# STM32_MPU_IOs.net
KiCad netlist of a schematic drawn in Altium Designer
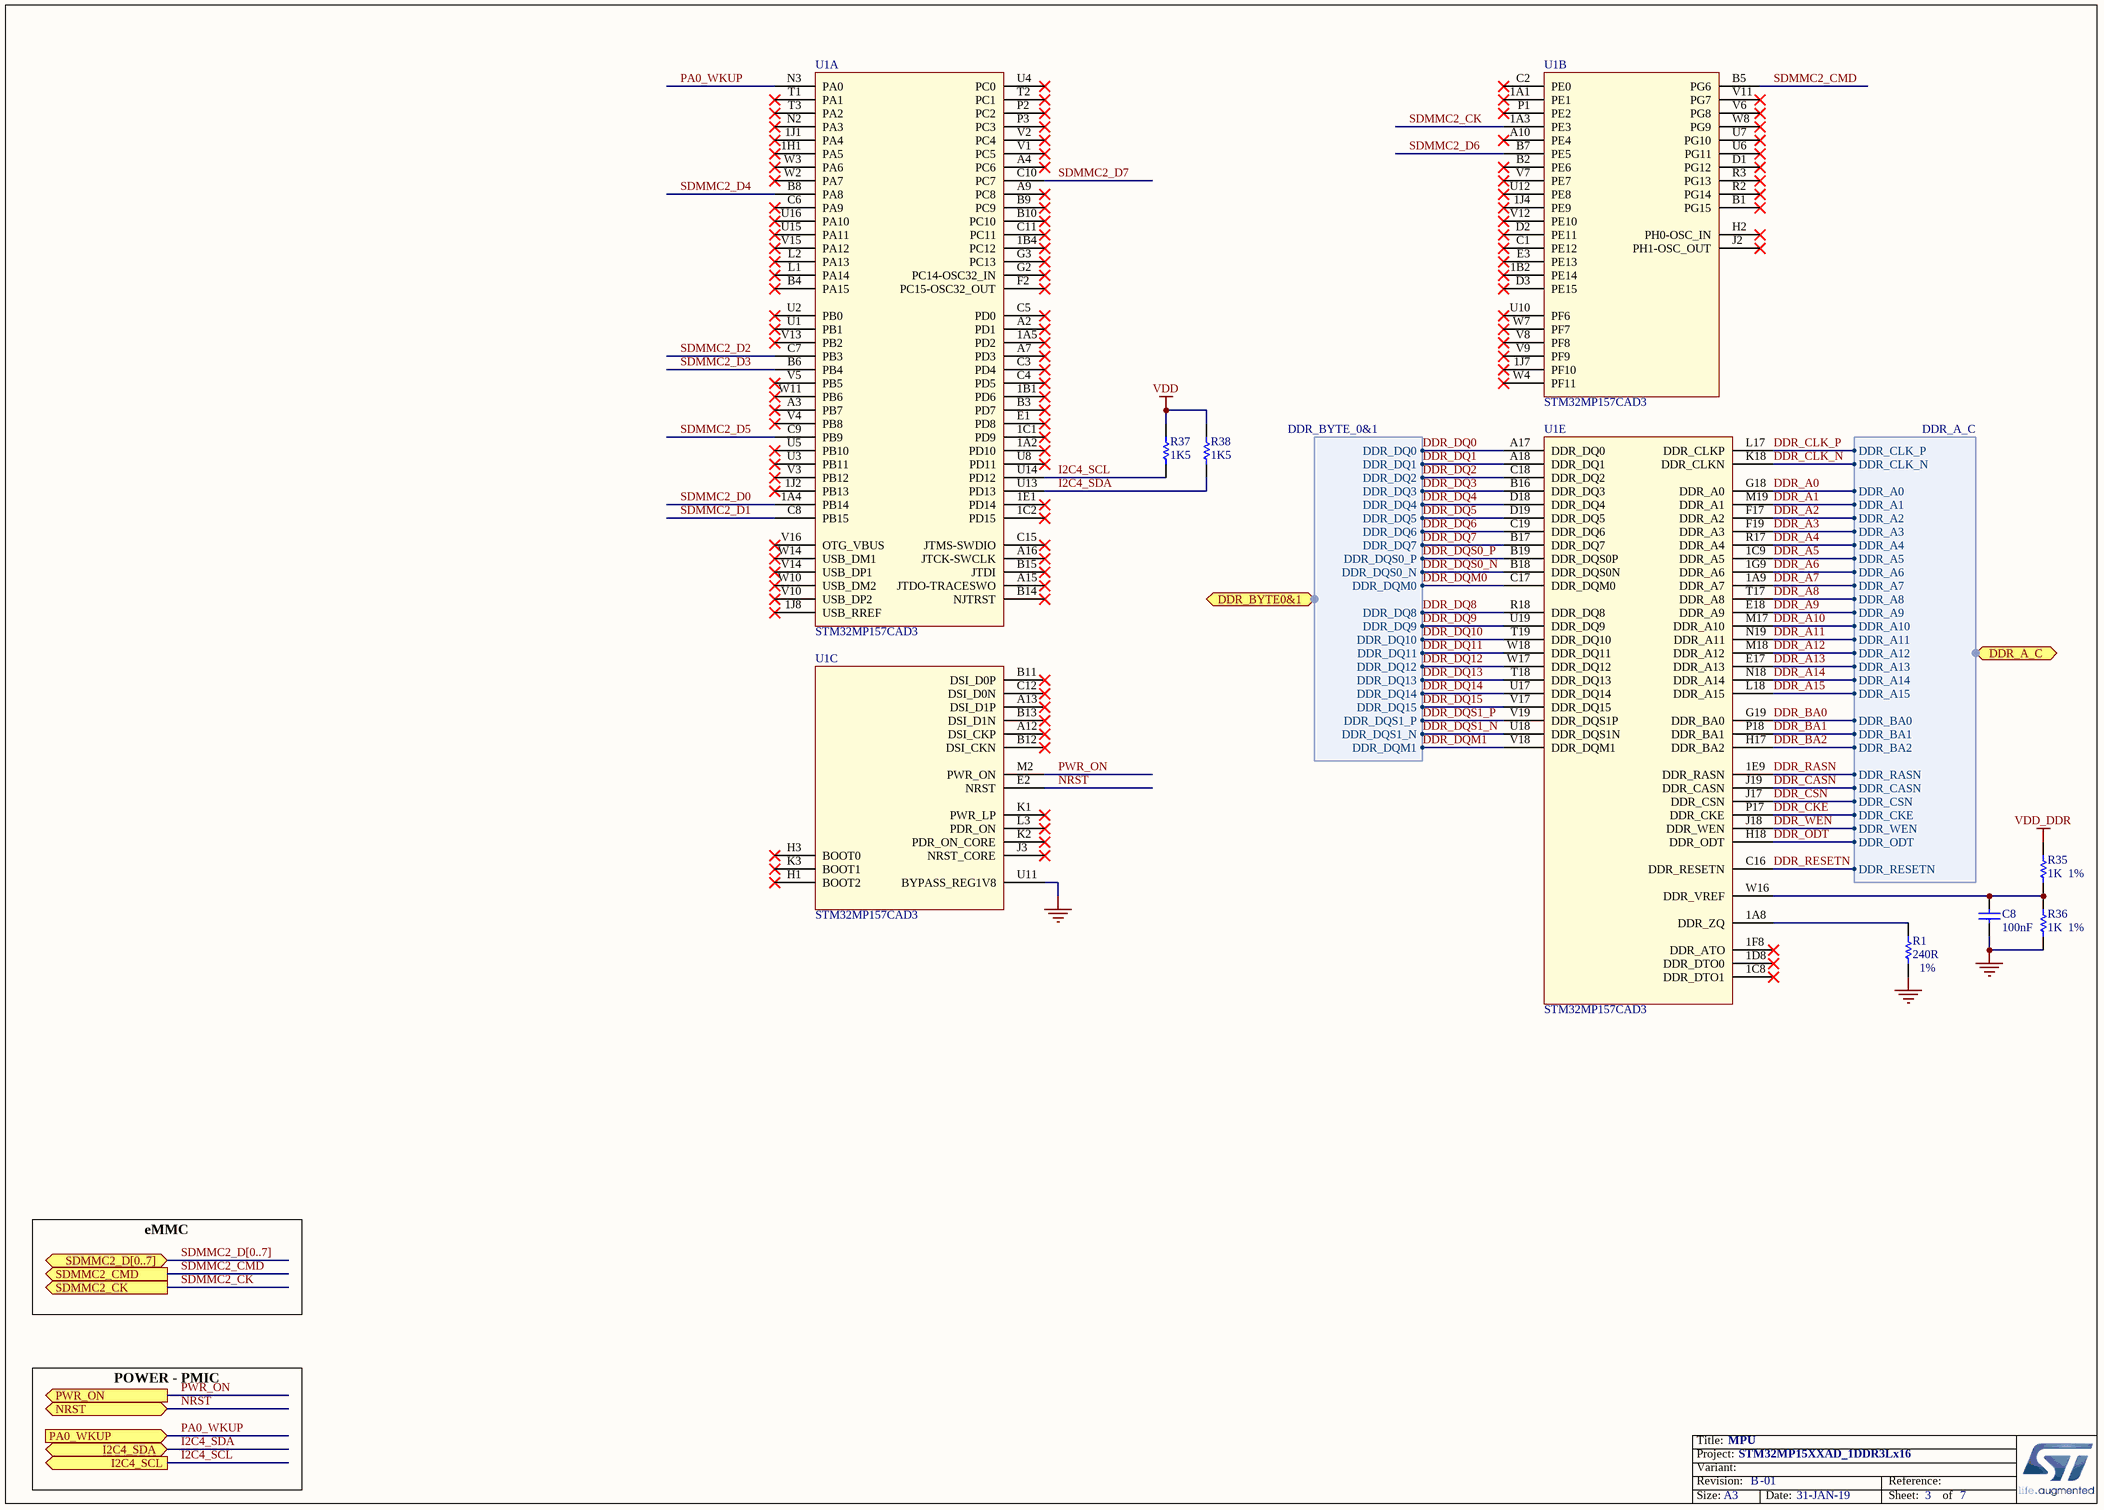
[diagram p0: STM32_MPU_IOs.SchDoc]

(export (version "E")
  (design (tool "Eeschema 10.0.6"))
  (components
    (comp (ref "C8")
      (value "100nF")
      (footprint "C0402")
      (description "Capacitor, MLCC, 100nF, 16V, X7R, 10%, 0402, T=0.5mm")
      (fields
        (field (name "INTERNAL_PART_NUMBER") "MCD-00006")
        (field (name "MANUFACTURER_PART_NUMBER") "CC0402KRX7R7BB104")
        (field (name "PROVIDED_BY") "SUBCO")
      )
      (libsource (lib "MCD_PARTS_database") (part "Capacitor"))
    )
    (comp (ref "R1")
      (value "240R")
      (footprint "R0402")
      (description "Resistor,240R,0402,1%,1/16W")
      (fields
        (field (name "INTERNAL_PART_NUMBER") "MCD-00120")
        (field (name "MANUFACTURER_PART_NUMBER") "RC0402FR-07240RL")
        (field (name "PROVIDED_BY") "SUBCO")
      )
      (libsource (lib "MCD_PARTS_database") (part "Resistor"))
    )
    (comp (ref "R35")
      (value "1K")
      (footprint "R0402")
      (description "Resistor,1K,0402,1%,1/16W")
      (fields
        (field (name "INTERNAL_PART_NUMBER") "MCD-00061")
        (field (name "MANUFACTURER_PART_NUMBER") "RC0402FR-071KL")
        (field (name "PROVIDED_BY") "SUBCO")
      )
      (libsource (lib "MCD_PARTS_database") (part "Resistor"))
    )
    (comp (ref "R36")
      (value "1K")
      (footprint "R0402")
      (description "Resistor,1K,0402,1%,1/16W")
      (fields
        (field (name "INTERNAL_PART_NUMBER") "MCD-00061")
        (field (name "MANUFACTURER_PART_NUMBER") "RC0402FR-071KL")
        (field (name "PROVIDED_BY") "SUBCO")
      )
      (libsource (lib "MCD_PARTS_database") (part "Resistor"))
    )
    (comp (ref "R37")
      (value "1K5")
      (footprint "R0402")
      (description "Resistor,1K5,0402,1%,1/16W")
      (fields
        (field (name "INTERNAL_PART_NUMBER") "MCD-00068")
        (field (name "MANUFACTURER_PART_NUMBER") "RC0402FR-071K5L")
        (field (name "PROVIDED_BY") "SUBCO")
      )
      (libsource (lib "MCD_PARTS_database") (part "Resistor"))
    )
    (comp (ref "R38")
      (value "1K5")
      (footprint "R0402")
      (description "Resistor,1K5,0402,1%,1/16W")
      (fields
        (field (name "INTERNAL_PART_NUMBER") "MCD-00068")
        (field (name "MANUFACTURER_PART_NUMBER") "RC0402FR-071K5L")
        (field (name "PROVIDED_BY") "SUBCO")
      )
      (libsource (lib "MCD_PARTS_database") (part "Resistor"))
    )
    (comp (ref "U1")
      (value "STM32MP157CAD3")
      (footprint "ICC_TFBGA257_10X10_STM32MP157CAD3_P050-065")
      (description "MPU TFBGA10x10 secure boot+crypto")
      (fields
        (field (name "INTERNAL_PART_NUMBER") "MCD-01144")
        (field (name "MANUFACTURER") "STMICROELECTRONICS")
        (field (name "PROVIDED_BY") "SUBCO with ST control")
      )
      (libsource (lib "MCD_PARTS_database") (part "STM32MP157CAD3"))
    )
  )
  (nets
    (net (code "3") (name "/DDR_A0") (class "Default")
      (node (ref "U1") (pin "G18") (pinfunction "DDR_A0_G18") (pintype "passive"))
    )
    (net (code "4") (name "/DDR_A1") (class "Default")
      (node (ref "U1") (pin "M19") (pinfunction "DDR_A1_M19") (pintype "passive"))
    )
    (net (code "5") (name "/DDR_A2") (class "Default")
      (node (ref "U1") (pin "F17") (pinfunction "DDR_A2_F17") (pintype "passive"))
    )
    (net (code "6") (name "/DDR_A3") (class "Default")
      (node (ref "U1") (pin "F19") (pinfunction "DDR_A3_F19") (pintype "passive"))
    )
    (net (code "7") (name "/DDR_A4") (class "Default")
      (node (ref "U1") (pin "R17") (pinfunction "DDR_A4_R17") (pintype "passive"))
    )
    (net (code "8") (name "/DDR_A5") (class "Default")
      (node (ref "U1") (pin "1C9") (pinfunction "DDR_A5_1C9") (pintype "passive"))
    )
    (net (code "9") (name "/DDR_A6") (class "Default")
      (node (ref "U1") (pin "1G9") (pinfunction "DDR_A6_1G9") (pintype "passive"))
    )
    (net (code "10") (name "/DDR_A7") (class "Default")
      (node (ref "U1") (pin "1A9") (pinfunction "DDR_A7_1A9") (pintype "passive"))
    )
    (net (code "11") (name "/DDR_A8") (class "Default")
      (node (ref "U1") (pin "T17") (pinfunction "DDR_A8_T17") (pintype "passive"))
    )
    (net (code "12") (name "/DDR_A9") (class "Default")
      (node (ref "U1") (pin "E18") (pinfunction "DDR_A9_E18") (pintype "passive"))
    )
    (net (code "13") (name "/DDR_A10") (class "Default")
      (node (ref "U1") (pin "M17") (pinfunction "DDR_A10_M17") (pintype "passive"))
    )
    (net (code "14") (name "/DDR_A11") (class "Default")
      (node (ref "U1") (pin "N19") (pinfunction "DDR_A11_N19") (pintype "passive"))
    )
    (net (code "15") (name "/DDR_A12") (class "Default")
      (node (ref "U1") (pin "M18") (pinfunction "DDR_A12_M18") (pintype "passive"))
    )
    (net (code "16") (name "/DDR_A13") (class "Default")
      (node (ref "U1") (pin "E17") (pinfunction "DDR_A13_E17") (pintype "passive"))
    )
    (net (code "17") (name "/DDR_A14") (class "Default")
      (node (ref "U1") (pin "N18") (pinfunction "DDR_A14_N18") (pintype "passive"))
    )
    (net (code "18") (name "/DDR_A15") (class "Default")
      (node (ref "U1") (pin "L18") (pinfunction "DDR_A15_L18") (pintype "passive"))
    )
    (net (code "19") (name "/DDR_BA0") (class "Default")
      (node (ref "U1") (pin "G19") (pinfunction "DDR_BA0_G19") (pintype "passive"))
    )
    (net (code "20") (name "/DDR_BA1") (class "Default")
      (node (ref "U1") (pin "P18") (pinfunction "DDR_BA1_P18") (pintype "passive"))
    )
    (net (code "21") (name "/DDR_BA2") (class "Default")
      (node (ref "U1") (pin "H17") (pinfunction "DDR_BA2_H17") (pintype "passive"))
    )
    (net (code "22") (name "/DDR_CASN") (class "Default")
      (node (ref "U1") (pin "J19") (pinfunction "DDR_CASN_J19") (pintype "passive"))
    )
    (net (code "23") (name "/DDR_CKE") (class "Default")
      (node (ref "U1") (pin "P17") (pinfunction "DDR_CKE_P17") (pintype "passive"))
    )
    (net (code "24") (name "/DDR_CLK_N") (class "Default")
      (node (ref "U1") (pin "K18") (pinfunction "DDR_CLKN_K18") (pintype "passive"))
    )
    (net (code "25") (name "/DDR_CLK_P") (class "Default")
      (node (ref "U1") (pin "L17") (pinfunction "DDR_CLKP_L17") (pintype "passive"))
    )
    (net (code "26") (name "/DDR_CSN") (class "Default")
      (node (ref "U1") (pin "J17") (pinfunction "DDR_CSN_J17") (pintype "passive"))
    )
    (net (code "27") (name "/DDR_DQ0") (class "Default")
      (node (ref "U1") (pin "A17") (pinfunction "DDR_DQ0_A17") (pintype "passive"))
    )
    (net (code "28") (name "/DDR_DQ1") (class "Default")
      (node (ref "U1") (pin "A18") (pinfunction "DDR_DQ1_A18") (pintype "passive"))
    )
    (net (code "29") (name "/DDR_DQ2") (class "Default")
      (node (ref "U1") (pin "C18") (pinfunction "DDR_DQ2_C18") (pintype "passive"))
    )
    (net (code "30") (name "/DDR_DQ3") (class "Default")
      (node (ref "U1") (pin "B16") (pinfunction "DDR_DQ3_B16") (pintype "passive"))
    )
    (net (code "31") (name "/DDR_DQ4") (class "Default")
      (node (ref "U1") (pin "D18") (pinfunction "DDR_DQ4_D18") (pintype "passive"))
    )
    (net (code "32") (name "/DDR_DQ5") (class "Default")
      (node (ref "U1") (pin "D19") (pinfunction "DDR_DQ5_D19") (pintype "passive"))
    )
    (net (code "33") (name "/DDR_DQ6") (class "Default")
      (node (ref "U1") (pin "C19") (pinfunction "DDR_DQ6_C19") (pintype "passive"))
    )
    (net (code "34") (name "/DDR_DQ7") (class "Default")
      (node (ref "U1") (pin "B17") (pinfunction "DDR_DQ7_B17") (pintype "passive"))
    )
    (net (code "35") (name "/DDR_DQ8") (class "Default")
      (node (ref "U1") (pin "R18") (pinfunction "DDR_DQ8_R18") (pintype "passive"))
    )
    (net (code "36") (name "/DDR_DQ9") (class "Default")
      (node (ref "U1") (pin "U19") (pinfunction "DDR_DQ9_U19") (pintype "passive"))
    )
    (net (code "37") (name "/DDR_DQ10") (class "Default")
      (node (ref "U1") (pin "T19") (pinfunction "DDR_DQ10_T19") (pintype "passive"))
    )
    (net (code "38") (name "/DDR_DQ11") (class "Default")
      (node (ref "U1") (pin "W18") (pinfunction "DDR_DQ11_W18") (pintype "passive"))
    )
    (net (code "39") (name "/DDR_DQ12") (class "Default")
      (node (ref "U1") (pin "W17") (pinfunction "DDR_DQ12_W17") (pintype "passive"))
    )
    (net (code "40") (name "/DDR_DQ13") (class "Default")
      (node (ref "U1") (pin "T18") (pinfunction "DDR_DQ13_T18") (pintype "passive"))
    )
    (net (code "41") (name "/DDR_DQ14") (class "Default")
      (node (ref "U1") (pin "U17") (pinfunction "DDR_DQ14_U17") (pintype "passive"))
    )
    (net (code "42") (name "/DDR_DQ15") (class "Default")
      (node (ref "U1") (pin "V17") (pinfunction "DDR_DQ15_V17") (pintype "passive"))
    )
    (net (code "43") (name "/DDR_DQM0") (class "Default")
      (node (ref "U1") (pin "C17") (pinfunction "DDR_DQM0_C17") (pintype "passive"))
    )
    (net (code "44") (name "/DDR_DQM1") (class "Default")
      (node (ref "U1") (pin "V18") (pinfunction "DDR_DQM1_V18") (pintype "passive"))
    )
    (net (code "45") (name "/DDR_DQS0_N") (class "Default")
      (node (ref "U1") (pin "B18") (pinfunction "DDR_DQS0N_B18") (pintype "passive"))
    )
    (net (code "46") (name "/DDR_DQS0_P") (class "Default")
      (node (ref "U1") (pin "B19") (pinfunction "DDR_DQS0P_B19") (pintype "passive"))
    )
    (net (code "47") (name "/DDR_DQS1_N") (class "Default")
      (node (ref "U1") (pin "U18") (pinfunction "DDR_DQS1N_U18") (pintype "passive"))
    )
    (net (code "48") (name "/DDR_DQS1_P") (class "Default")
      (node (ref "U1") (pin "V19") (pinfunction "DDR_DQS1P_V19") (pintype "passive"))
    )
    (net (code "49") (name "/DDR_ODT") (class "Default")
      (node (ref "U1") (pin "H18") (pinfunction "DDR_ODT_H18") (pintype "passive"))
    )
    (net (code "50") (name "/DDR_RASN") (class "Default")
      (node (ref "U1") (pin "1E9") (pinfunction "DDR_RASN_1E9") (pintype "passive"))
    )
    (net (code "51") (name "/DDR_RESETN") (class "Default")
      (node (ref "U1") (pin "C16") (pinfunction "DDR_RESETN_C16") (pintype "passive"))
    )
    (net (code "52") (name "/DDR_WEN") (class "Default")
      (node (ref "U1") (pin "J18") (pinfunction "DDR_WEN_J18") (pintype "passive"))
    )
    (net (code "53") (name "/I2C4_SCL") (class "Default")
      (node (ref "R37") (pin "2") (pinfunction "2_2") (pintype "passive"))
      (node (ref "U1") (pin "U14") (pinfunction "PD12_U14") (pintype "passive"))
    )
    (net (code "54") (name "/I2C4_SDA") (class "Default")
      (node (ref "R38") (pin "2") (pinfunction "2_2") (pintype "passive"))
      (node (ref "U1") (pin "U13") (pinfunction "PD13_U13") (pintype "passive"))
    )
    (net (code "55") (name "/NRST") (class "Default")
      (node (ref "U1") (pin "E2") (pinfunction "NRST_E2") (pintype "passive"))
    )
    (net (code "56") (name "/PA0_WKUP") (class "Default")
      (node (ref "U1") (pin "N3") (pinfunction "PA0_N3") (pintype "passive"))
    )
    (net (code "57") (name "/PWR_ON") (class "Default")
      (node (ref "U1") (pin "M2") (pinfunction "PWR_ON_M2") (pintype "passive"))
    )
    (net (code "58") (name "/SDMMC2_CK") (class "Default")
      (node (ref "U1") (pin "1A3") (pinfunction "PE3_1A3") (pintype "passive"))
    )
    (net (code "59") (name "/SDMMC2_CMD") (class "Default")
      (node (ref "U1") (pin "B5") (pinfunction "PG6_B5") (pintype "passive"))
    )
    (net (code "60") (name "/SDMMC2_D0") (class "Default")
      (node (ref "U1") (pin "1A4") (pinfunction "PB14_1A4") (pintype "passive"))
    )
    (net (code "61") (name "/SDMMC2_D1") (class "Default")
      (node (ref "U1") (pin "C8") (pinfunction "PB15_C8") (pintype "passive"))
    )
    (net (code "62") (name "/SDMMC2_D2") (class "Default")
      (node (ref "U1") (pin "C7") (pinfunction "PB3_C7") (pintype "passive"))
    )
    (net (code "63") (name "/SDMMC2_D3") (class "Default")
      (node (ref "U1") (pin "B6") (pinfunction "PB4_B6") (pintype "passive"))
    )
    (net (code "64") (name "/SDMMC2_D4") (class "Default")
      (node (ref "U1") (pin "B8") (pinfunction "PA8_B8") (pintype "passive"))
    )
    (net (code "65") (name "/SDMMC2_D5") (class "Default")
      (node (ref "U1") (pin "C9") (pinfunction "PB9_C9") (pintype "passive"))
    )
    (net (code "66") (name "/SDMMC2_D6") (class "Default")
      (node (ref "U1") (pin "B7") (pinfunction "PE5_B7") (pintype "passive"))
    )
    (net (code "67") (name "/SDMMC2_D7") (class "Default")
      (node (ref "U1") (pin "C10") (pinfunction "PC7_C10") (pintype "passive"))
    )
    (net (code "71") (name "GND") (class "Default")
      (node (ref "C8") (pin "1") (pinfunction "1_1") (pintype "passive"))
      (node (ref "R1") (pin "1") (pinfunction "1_1") (pintype "passive"))
      (node (ref "R36") (pin "1") (pinfunction "1_1") (pintype "passive"))
      (node (ref "U1") (pin "U11") (pinfunction "BYPASS_REG1V8_U11") (pintype "passive"))
    )
    (net (code "72") (name "Net-(U1E-DDR_VREF)") (class "Default")
      (node (ref "C8") (pin "2") (pinfunction "2_2") (pintype "passive"))
      (node (ref "R35") (pin "1") (pinfunction "1_1") (pintype "passive"))
      (node (ref "R36") (pin "2") (pinfunction "2_2") (pintype "passive"))
      (node (ref "U1") (pin "W16") (pinfunction "DDR_VREF_W16") (pintype "passive"))
    )
    (net (code "73") (name "Net-(U1E-DDR_ZQ)") (class "Default")
      (node (ref "R1") (pin "2") (pinfunction "2_2") (pintype "passive"))
      (node (ref "U1") (pin "1A8") (pinfunction "DDR_ZQ_1A8") (pintype "passive"))
    )
    (net (code "74") (name "VDD") (class "Default")
      (node (ref "R37") (pin "1") (pinfunction "1_1") (pintype "passive"))
      (node (ref "R38") (pin "1") (pinfunction "1_1") (pintype "passive"))
    )
    (net (code "75") (name "VDD_DDR") (class "Default")
      (node (ref "R35") (pin "2") (pinfunction "2_2") (pintype "passive"))
    )
    (net (code "76") (name "unconnected-(U1A-JTCK-SWCLK-PadA16)") (class "Default")
      (node (ref "U1") (pin "A16") (pinfunction "JTCK-SWCLK_A16") (pintype "passive+no_connect"))
    )
    (net (code "77") (name "unconnected-(U1A-JTDI-PadB15)") (class "Default")
      (node (ref "U1") (pin "B15") (pinfunction "JTDI_B15") (pintype "passive+no_connect"))
    )
    (net (code "78") (name "unconnected-(U1A-JTDO-TRACESWO-PadA15)") (class "Default")
      (node (ref "U1") (pin "A15") (pinfunction "JTDO-TRACESWO_A15") (pintype "passive+no_connect"))
    )
    (net (code "79") (name "unconnected-(U1A-JTMS-SWDIO-PadC15)") (class "Default")
      (node (ref "U1") (pin "C15") (pinfunction "JTMS-SWDIO_C15") (pintype "passive+no_connect"))
    )
    (net (code "80") (name "unconnected-(U1A-NJTRST-PadB14)") (class "Default")
      (node (ref "U1") (pin "B14") (pinfunction "NJTRST_B14") (pintype "passive+no_connect"))
    )
    (net (code "81") (name "unconnected-(U1A-OTG_VBUS-PadV16)") (class "Default")
      (node (ref "U1") (pin "V16") (pinfunction "OTG_VBUS_V16") (pintype "passive+no_connect"))
    )
    (net (code "82") (name "unconnected-(U1A-PA1-PadT1)") (class "Default")
      (node (ref "U1") (pin "T1") (pinfunction "PA1_T1") (pintype "passive+no_connect"))
    )
    (net (code "83") (name "unconnected-(U1A-PA2-PadT3)") (class "Default")
      (node (ref "U1") (pin "T3") (pinfunction "PA2_T3") (pintype "passive+no_connect"))
    )
    (net (code "84") (name "unconnected-(U1A-PA3-PadN2)") (class "Default")
      (node (ref "U1") (pin "N2") (pinfunction "PA3_N2") (pintype "passive+no_connect"))
    )
    (net (code "85") (name "unconnected-(U1A-PA4-Pad1J1)") (class "Default")
      (node (ref "U1") (pin "1J1") (pinfunction "PA4_1J1") (pintype "passive+no_connect"))
    )
    (net (code "86") (name "unconnected-(U1A-PA5-Pad1H1)") (class "Default")
      (node (ref "U1") (pin "1H1") (pinfunction "PA5_1H1") (pintype "passive+no_connect"))
    )
    (net (code "87") (name "unconnected-(U1A-PA6-PadW3)") (class "Default")
      (node (ref "U1") (pin "W3") (pinfunction "PA6_W3") (pintype "passive+no_connect"))
    )
    (net (code "88") (name "unconnected-(U1A-PA7-PadW2)") (class "Default")
      (node (ref "U1") (pin "W2") (pinfunction "PA7_W2") (pintype "passive+no_connect"))
    )
    (net (code "89") (name "unconnected-(U1A-PA9-PadC6)") (class "Default")
      (node (ref "U1") (pin "C6") (pinfunction "PA9_C6") (pintype "passive+no_connect"))
    )
    (net (code "90") (name "unconnected-(U1A-PA10-PadU16)") (class "Default")
      (node (ref "U1") (pin "U16") (pinfunction "PA10_U16") (pintype "passive+no_connect"))
    )
    (net (code "91") (name "unconnected-(U1A-PA11-PadU15)") (class "Default")
      (node (ref "U1") (pin "U15") (pinfunction "PA11_U15") (pintype "passive+no_connect"))
    )
    (net (code "92") (name "unconnected-(U1A-PA12-PadV15)") (class "Default")
      (node (ref "U1") (pin "V15") (pinfunction "PA12_V15") (pintype "passive+no_connect"))
    )
    (net (code "93") (name "unconnected-(U1A-PA13-PadL2)") (class "Default")
      (node (ref "U1") (pin "L2") (pinfunction "PA13_L2") (pintype "passive+no_connect"))
    )
    (net (code "94") (name "unconnected-(U1A-PA14-PadL1)") (class "Default")
      (node (ref "U1") (pin "L1") (pinfunction "PA14_L1") (pintype "passive+no_connect"))
    )
    (net (code "95") (name "unconnected-(U1A-PA15-PadB4)") (class "Default")
      (node (ref "U1") (pin "B4") (pinfunction "PA15_B4") (pintype "passive+no_connect"))
    )
    (net (code "96") (name "unconnected-(U1A-PB0-PadU2)") (class "Default")
      (node (ref "U1") (pin "U2") (pinfunction "PB0_U2") (pintype "passive+no_connect"))
    )
    (net (code "97") (name "unconnected-(U1A-PB1-PadU1)") (class "Default")
      (node (ref "U1") (pin "U1") (pinfunction "PB1_U1") (pintype "passive+no_connect"))
    )
    (net (code "98") (name "unconnected-(U1A-PB2-PadV13)") (class "Default")
      (node (ref "U1") (pin "V13") (pinfunction "PB2_V13") (pintype "passive+no_connect"))
    )
    (net (code "99") (name "unconnected-(U1A-PB5-PadV5)") (class "Default")
      (node (ref "U1") (pin "V5") (pinfunction "PB5_V5") (pintype "passive+no_connect"))
    )
    (net (code "100") (name "unconnected-(U1A-PB6-PadW11)") (class "Default")
      (node (ref "U1") (pin "W11") (pinfunction "PB6_W11") (pintype "passive+no_connect"))
    )
    (net (code "101") (name "unconnected-(U1A-PB7-PadA3)") (class "Default")
      (node (ref "U1") (pin "A3") (pinfunction "PB7_A3") (pintype "passive+no_connect"))
    )
    (net (code "102") (name "unconnected-(U1A-PB8-PadV4)") (class "Default")
      (node (ref "U1") (pin "V4") (pinfunction "PB8_V4") (pintype "passive+no_connect"))
    )
    (net (code "103") (name "unconnected-(U1A-PB10-PadU5)") (class "Default")
      (node (ref "U1") (pin "U5") (pinfunction "PB10_U5") (pintype "passive+no_connect"))
    )
    (net (code "104") (name "unconnected-(U1A-PB11-PadU3)") (class "Default")
      (node (ref "U1") (pin "U3") (pinfunction "PB11_U3") (pintype "passive+no_connect"))
    )
    (net (code "105") (name "unconnected-(U1A-PB12-PadV3)") (class "Default")
      (node (ref "U1") (pin "V3") (pinfunction "PB12_V3") (pintype "passive+no_connect"))
    )
    (net (code "106") (name "unconnected-(U1A-PB13-Pad1J2)") (class "Default")
      (node (ref "U1") (pin "1J2") (pinfunction "PB13_1J2") (pintype "passive+no_connect"))
    )
    (net (code "107") (name "unconnected-(U1A-PC0-PadU4)") (class "Default")
      (node (ref "U1") (pin "U4") (pinfunction "PC0_U4") (pintype "passive+no_connect"))
    )
    (net (code "108") (name "unconnected-(U1A-PC1-PadT2)") (class "Default")
      (node (ref "U1") (pin "T2") (pinfunction "PC1_T2") (pintype "passive+no_connect"))
    )
    (net (code "109") (name "unconnected-(U1A-PC2-PadP2)") (class "Default")
      (node (ref "U1") (pin "P2") (pinfunction "PC2_P2") (pintype "passive+no_connect"))
    )
    (net (code "110") (name "unconnected-(U1A-PC3-PadP3)") (class "Default")
      (node (ref "U1") (pin "P3") (pinfunction "PC3_P3") (pintype "passive+no_connect"))
    )
    (net (code "111") (name "unconnected-(U1A-PC4-PadV2)") (class "Default")
      (node (ref "U1") (pin "V2") (pinfunction "PC4_V2") (pintype "passive+no_connect"))
    )
    (net (code "112") (name "unconnected-(U1A-PC5-PadV1)") (class "Default")
      (node (ref "U1") (pin "V1") (pinfunction "PC5_V1") (pintype "passive+no_connect"))
    )
    (net (code "113") (name "unconnected-(U1A-PC6-PadA4)") (class "Default")
      (node (ref "U1") (pin "A4") (pinfunction "PC6_A4") (pintype "passive+no_connect"))
    )
    (net (code "114") (name "unconnected-(U1A-PC8-PadA9)") (class "Default")
      (node (ref "U1") (pin "A9") (pinfunction "PC8_A9") (pintype "passive+no_connect"))
    )
    (net (code "115") (name "unconnected-(U1A-PC9-PadB9)") (class "Default")
      (node (ref "U1") (pin "B9") (pinfunction "PC9_B9") (pintype "passive+no_connect"))
    )
    (net (code "116") (name "unconnected-(U1A-PC10-PadB10)") (class "Default")
      (node (ref "U1") (pin "B10") (pinfunction "PC10_B10") (pintype "passive+no_connect"))
    )
    (net (code "117") (name "unconnected-(U1A-PC11-PadC11)") (class "Default")
      (node (ref "U1") (pin "C11") (pinfunction "PC11_C11") (pintype "passive+no_connect"))
    )
    (net (code "118") (name "unconnected-(U1A-PC12-Pad1B4)") (class "Default")
      (node (ref "U1") (pin "1B4") (pinfunction "PC12_1B4") (pintype "passive+no_connect"))
    )
    (net (code "119") (name "unconnected-(U1A-PC13-PadG3)") (class "Default")
      (node (ref "U1") (pin "G3") (pinfunction "PC13_G3") (pintype "passive+no_connect"))
    )
    (net (code "120") (name "unconnected-(U1A-PC14-OSC32_IN-PadG2)") (class "Default")
      (node (ref "U1") (pin "G2") (pinfunction "PC14-OSC32_IN_G2") (pintype "passive+no_connect"))
    )
    (net (code "121") (name "unconnected-(U1A-PC15-OSC32_OUT-PadF2)") (class "Default")
      (node (ref "U1") (pin "F2") (pinfunction "PC15-OSC32_OUT_F2") (pintype "passive+no_connect"))
    )
    (net (code "122") (name "unconnected-(U1A-PD0-PadC5)") (class "Default")
      (node (ref "U1") (pin "C5") (pinfunction "PD0_C5") (pintype "passive+no_connect"))
    )
    (net (code "123") (name "unconnected-(U1A-PD1-PadA2)") (class "Default")
      (node (ref "U1") (pin "A2") (pinfunction "PD1_A2") (pintype "passive+no_connect"))
    )
    (net (code "124") (name "unconnected-(U1A-PD2-Pad1A5)") (class "Default")
      (node (ref "U1") (pin "1A5") (pinfunction "PD2_1A5") (pintype "passive+no_connect"))
    )
    (net (code "125") (name "unconnected-(U1A-PD3-PadA7)") (class "Default")
      (node (ref "U1") (pin "A7") (pinfunction "PD3_A7") (pintype "passive+no_connect"))
    )
    (net (code "126") (name "unconnected-(U1A-PD4-PadC3)") (class "Default")
      (node (ref "U1") (pin "C3") (pinfunction "PD4_C3") (pintype "passive+no_connect"))
    )
    (net (code "127") (name "unconnected-(U1A-PD5-PadC4)") (class "Default")
      (node (ref "U1") (pin "C4") (pinfunction "PD5_C4") (pintype "passive+no_connect"))
    )
    (net (code "128") (name "unconnected-(U1A-PD6-Pad1B1)") (class "Default")
      (node (ref "U1") (pin "1B1") (pinfunction "PD6_1B1") (pintype "passive+no_connect"))
    )
    (net (code "129") (name "unconnected-(U1A-PD7-PadB3)") (class "Default")
      (node (ref "U1") (pin "B3") (pinfunction "PD7_B3") (pintype "passive+no_connect"))
    )
    (net (code "130") (name "unconnected-(U1A-PD8-PadE1)") (class "Default")
      (node (ref "U1") (pin "E1") (pinfunction "PD8_E1") (pintype "passive+no_connect"))
    )
    (net (code "131") (name "unconnected-(U1A-PD9-Pad1C1)") (class "Default")
      (node (ref "U1") (pin "1C1") (pinfunction "PD9_1C1") (pintype "passive+no_connect"))
    )
    (net (code "132") (name "unconnected-(U1A-PD10-Pad1A2)") (class "Default")
      (node (ref "U1") (pin "1A2") (pinfunction "PD10_1A2") (pintype "passive+no_connect"))
    )
    (net (code "133") (name "unconnected-(U1A-PD11-PadU8)") (class "Default")
      (node (ref "U1") (pin "U8") (pinfunction "PD11_U8") (pintype "passive+no_connect"))
    )
    (net (code "134") (name "unconnected-(U1A-PD14-Pad1E1)") (class "Default")
      (node (ref "U1") (pin "1E1") (pinfunction "PD14_1E1") (pintype "passive+no_connect"))
    )
    (net (code "135") (name "unconnected-(U1A-PD15-Pad1C2)") (class "Default")
      (node (ref "U1") (pin "1C2") (pinfunction "PD15_1C2") (pintype "passive+no_connect"))
    )
    (net (code "136") (name "unconnected-(U1A-USB_DM1-PadW14)") (class "Default")
      (node (ref "U1") (pin "W14") (pinfunction "USB_DM1_W14") (pintype "passive+no_connect"))
    )
    (net (code "137") (name "unconnected-(U1A-USB_DM2-PadW10)") (class "Default")
      (node (ref "U1") (pin "W10") (pinfunction "USB_DM2_W10") (pintype "passive+no_connect"))
    )
    (net (code "138") (name "unconnected-(U1A-USB_DP1-PadV14)") (class "Default")
      (node (ref "U1") (pin "V14") (pinfunction "USB_DP1_V14") (pintype "passive+no_connect"))
    )
    (net (code "139") (name "unconnected-(U1A-USB_DP2-PadV10)") (class "Default")
      (node (ref "U1") (pin "V10") (pinfunction "USB_DP2_V10") (pintype "passive+no_connect"))
    )
    (net (code "140") (name "unconnected-(U1A-USB_RREF-Pad1J8)") (class "Default")
      (node (ref "U1") (pin "1J8") (pinfunction "USB_RREF_1J8") (pintype "passive+no_connect"))
    )
    (net (code "141") (name "unconnected-(U1B-PE0-PadC2)") (class "Default")
      (node (ref "U1") (pin "C2") (pinfunction "PE0_C2") (pintype "passive+no_connect"))
    )
    (net (code "142") (name "unconnected-(U1B-PE1-Pad1A1)") (class "Default")
      (node (ref "U1") (pin "1A1") (pinfunction "PE1_1A1") (pintype "passive+no_connect"))
    )
    (net (code "143") (name "unconnected-(U1B-PE2-PadP1)") (class "Default")
      (node (ref "U1") (pin "P1") (pinfunction "PE2_P1") (pintype "passive+no_connect"))
    )
    (net (code "144") (name "unconnected-(U1B-PE4-PadA10)") (class "Default")
      (node (ref "U1") (pin "A10") (pinfunction "PE4_A10") (pintype "passive+no_connect"))
    )
    (net (code "145") (name "unconnected-(U1B-PE6-PadB2)") (class "Default")
      (node (ref "U1") (pin "B2") (pinfunction "PE6_B2") (pintype "passive+no_connect"))
    )
    (net (code "146") (name "unconnected-(U1B-PE7-PadV7)") (class "Default")
      (node (ref "U1") (pin "V7") (pinfunction "PE7_V7") (pintype "passive+no_connect"))
    )
    (net (code "147") (name "unconnected-(U1B-PE8-PadU12)") (class "Default")
      (node (ref "U1") (pin "U12") (pinfunction "PE8_U12") (pintype "passive+no_connect"))
    )
    (net (code "148") (name "unconnected-(U1B-PE9-Pad1J4)") (class "Default")
      (node (ref "U1") (pin "1J4") (pinfunction "PE9_1J4") (pintype "passive+no_connect"))
    )
    (net (code "149") (name "unconnected-(U1B-PE10-PadV12)") (class "Default")
      (node (ref "U1") (pin "V12") (pinfunction "PE10_V12") (pintype "passive+no_connect"))
    )
    (net (code "150") (name "unconnected-(U1B-PE11-PadD2)") (class "Default")
      (node (ref "U1") (pin "D2") (pinfunction "PE11_D2") (pintype "passive+no_connect"))
    )
    (net (code "151") (name "unconnected-(U1B-PE12-PadC1)") (class "Default")
      (node (ref "U1") (pin "C1") (pinfunction "PE12_C1") (pintype "passive+no_connect"))
    )
    (net (code "152") (name "unconnected-(U1B-PE13-PadE3)") (class "Default")
      (node (ref "U1") (pin "E3") (pinfunction "PE13_E3") (pintype "passive+no_connect"))
    )
    (net (code "153") (name "unconnected-(U1B-PE14-Pad1B2)") (class "Default")
      (node (ref "U1") (pin "1B2") (pinfunction "PE14_1B2") (pintype "passive+no_connect"))
    )
    (net (code "154") (name "unconnected-(U1B-PE15-PadD3)") (class "Default")
      (node (ref "U1") (pin "D3") (pinfunction "PE15_D3") (pintype "passive+no_connect"))
    )
    (net (code "155") (name "unconnected-(U1B-PF6-PadU10)") (class "Default")
      (node (ref "U1") (pin "U10") (pinfunction "PF6_U10") (pintype "passive+no_connect"))
    )
    (net (code "156") (name "unconnected-(U1B-PF7-PadW7)") (class "Default")
      (node (ref "U1") (pin "W7") (pinfunction "PF7_W7") (pintype "passive+no_connect"))
    )
    (net (code "157") (name "unconnected-(U1B-PF8-PadV8)") (class "Default")
      (node (ref "U1") (pin "V8") (pinfunction "PF8_V8") (pintype "passive+no_connect"))
    )
    (net (code "158") (name "unconnected-(U1B-PF9-PadV9)") (class "Default")
      (node (ref "U1") (pin "V9") (pinfunction "PF9_V9") (pintype "passive+no_connect"))
    )
    (net (code "159") (name "unconnected-(U1B-PF10-Pad1J7)") (class "Default")
      (node (ref "U1") (pin "1J7") (pinfunction "PF10_1J7") (pintype "passive+no_connect"))
    )
    (net (code "160") (name "unconnected-(U1B-PF11-PadW4)") (class "Default")
      (node (ref "U1") (pin "W4") (pinfunction "PF11_W4") (pintype "passive+no_connect"))
    )
    (net (code "161") (name "unconnected-(U1B-PG7-PadV11)") (class "Default")
      (node (ref "U1") (pin "V11") (pinfunction "PG7_V11") (pintype "passive+no_connect"))
    )
    (net (code "162") (name "unconnected-(U1B-PG8-PadV6)") (class "Default")
      (node (ref "U1") (pin "V6") (pinfunction "PG8_V6") (pintype "passive+no_connect"))
    )
    (net (code "163") (name "unconnected-(U1B-PG9-PadW8)") (class "Default")
      (node (ref "U1") (pin "W8") (pinfunction "PG9_W8") (pintype "passive+no_connect"))
    )
    (net (code "164") (name "unconnected-(U1B-PG10-PadU7)") (class "Default")
      (node (ref "U1") (pin "U7") (pinfunction "PG10_U7") (pintype "passive+no_connect"))
    )
    (net (code "165") (name "unconnected-(U1B-PG11-PadU6)") (class "Default")
      (node (ref "U1") (pin "U6") (pinfunction "PG11_U6") (pintype "passive+no_connect"))
    )
    (net (code "166") (name "unconnected-(U1B-PG12-PadD1)") (class "Default")
      (node (ref "U1") (pin "D1") (pinfunction "PG12_D1") (pintype "passive+no_connect"))
    )
    (net (code "167") (name "unconnected-(U1B-PG13-PadR3)") (class "Default")
      (node (ref "U1") (pin "R3") (pinfunction "PG13_R3") (pintype "passive+no_connect"))
    )
    (net (code "168") (name "unconnected-(U1B-PG14-PadR2)") (class "Default")
      (node (ref "U1") (pin "R2") (pinfunction "PG14_R2") (pintype "passive+no_connect"))
    )
    (net (code "169") (name "unconnected-(U1B-PG15-PadB1)") (class "Default")
      (node (ref "U1") (pin "B1") (pinfunction "PG15_B1") (pintype "passive+no_connect"))
    )
    (net (code "170") (name "unconnected-(U1B-PH0-OSC_IN-PadH2)") (class "Default")
      (node (ref "U1") (pin "H2") (pinfunction "PH0-OSC_IN_H2") (pintype "passive+no_connect"))
    )
    (net (code "171") (name "unconnected-(U1B-PH1-OSC_OUT-PadJ2)") (class "Default")
      (node (ref "U1") (pin "J2") (pinfunction "PH1-OSC_OUT_J2") (pintype "passive+no_connect"))
    )
    (net (code "172") (name "unconnected-(U1C-BOOT0-PadH3)") (class "Default")
      (node (ref "U1") (pin "H3") (pinfunction "BOOT0_H3") (pintype "passive+no_connect"))
    )
    (net (code "173") (name "unconnected-(U1C-BOOT1-PadK3)") (class "Default")
      (node (ref "U1") (pin "K3") (pinfunction "BOOT1_K3") (pintype "passive+no_connect"))
    )
    (net (code "174") (name "unconnected-(U1C-BOOT2-PadH1)") (class "Default")
      (node (ref "U1") (pin "H1") (pinfunction "BOOT2_H1") (pintype "passive+no_connect"))
    )
    (net (code "175") (name "unconnected-(U1C-DSI_CKN-PadB12)") (class "Default")
      (node (ref "U1") (pin "B12") (pinfunction "DSI_CKN_B12") (pintype "passive+no_connect"))
    )
    (net (code "176") (name "unconnected-(U1C-DSI_CKP-PadA12)") (class "Default")
      (node (ref "U1") (pin "A12") (pinfunction "DSI_CKP_A12") (pintype "passive+no_connect"))
    )
    (net (code "177") (name "unconnected-(U1C-DSI_D0N-PadC12)") (class "Default")
      (node (ref "U1") (pin "C12") (pinfunction "DSI_D0N_C12") (pintype "passive+no_connect"))
    )
    (net (code "178") (name "unconnected-(U1C-DSI_D0P-PadB11)") (class "Default")
      (node (ref "U1") (pin "B11") (pinfunction "DSI_D0P_B11") (pintype "passive+no_connect"))
    )
    (net (code "179") (name "unconnected-(U1C-DSI_D1N-PadB13)") (class "Default")
      (node (ref "U1") (pin "B13") (pinfunction "DSI_D1N_B13") (pintype "passive+no_connect"))
    )
    (net (code "180") (name "unconnected-(U1C-DSI_D1P-PadA13)") (class "Default")
      (node (ref "U1") (pin "A13") (pinfunction "DSI_D1P_A13") (pintype "passive+no_connect"))
    )
    (net (code "181") (name "unconnected-(U1C-NRST_CORE-PadJ3)") (class "Default")
      (node (ref "U1") (pin "J3") (pinfunction "NRST_CORE_J3") (pintype "passive+no_connect"))
    )
    (net (code "182") (name "unconnected-(U1C-PDR_ON-PadL3)") (class "Default")
      (node (ref "U1") (pin "L3") (pinfunction "PDR_ON_L3") (pintype "passive+no_connect"))
    )
    (net (code "183") (name "unconnected-(U1C-PDR_ON_CORE-PadK2)") (class "Default")
      (node (ref "U1") (pin "K2") (pinfunction "PDR_ON_CORE_K2") (pintype "passive+no_connect"))
    )
    (net (code "184") (name "unconnected-(U1C-PWR_LP-PadK1)") (class "Default")
      (node (ref "U1") (pin "K1") (pinfunction "PWR_LP_K1") (pintype "passive+no_connect"))
    )
    (net (code "185") (name "unconnected-(U1E-DDR_ATO-Pad1F8)") (class "Default")
      (node (ref "U1") (pin "1F8") (pinfunction "DDR_ATO_1F8") (pintype "passive+no_connect"))
    )
    (net (code "186") (name "unconnected-(U1E-DDR_DTO0-Pad1D8)") (class "Default")
      (node (ref "U1") (pin "1D8") (pinfunction "DDR_DTO0_1D8") (pintype "passive+no_connect"))
    )
    (net (code "187") (name "unconnected-(U1E-DDR_DTO1-Pad1C8)") (class "Default")
      (node (ref "U1") (pin "1C8") (pinfunction "DDR_DTO1_1C8") (pintype "passive+no_connect"))
    )
  )
)
